# uController_n_Ethernet.net
KiCad netlist of a schematic drawn in Altium Designer
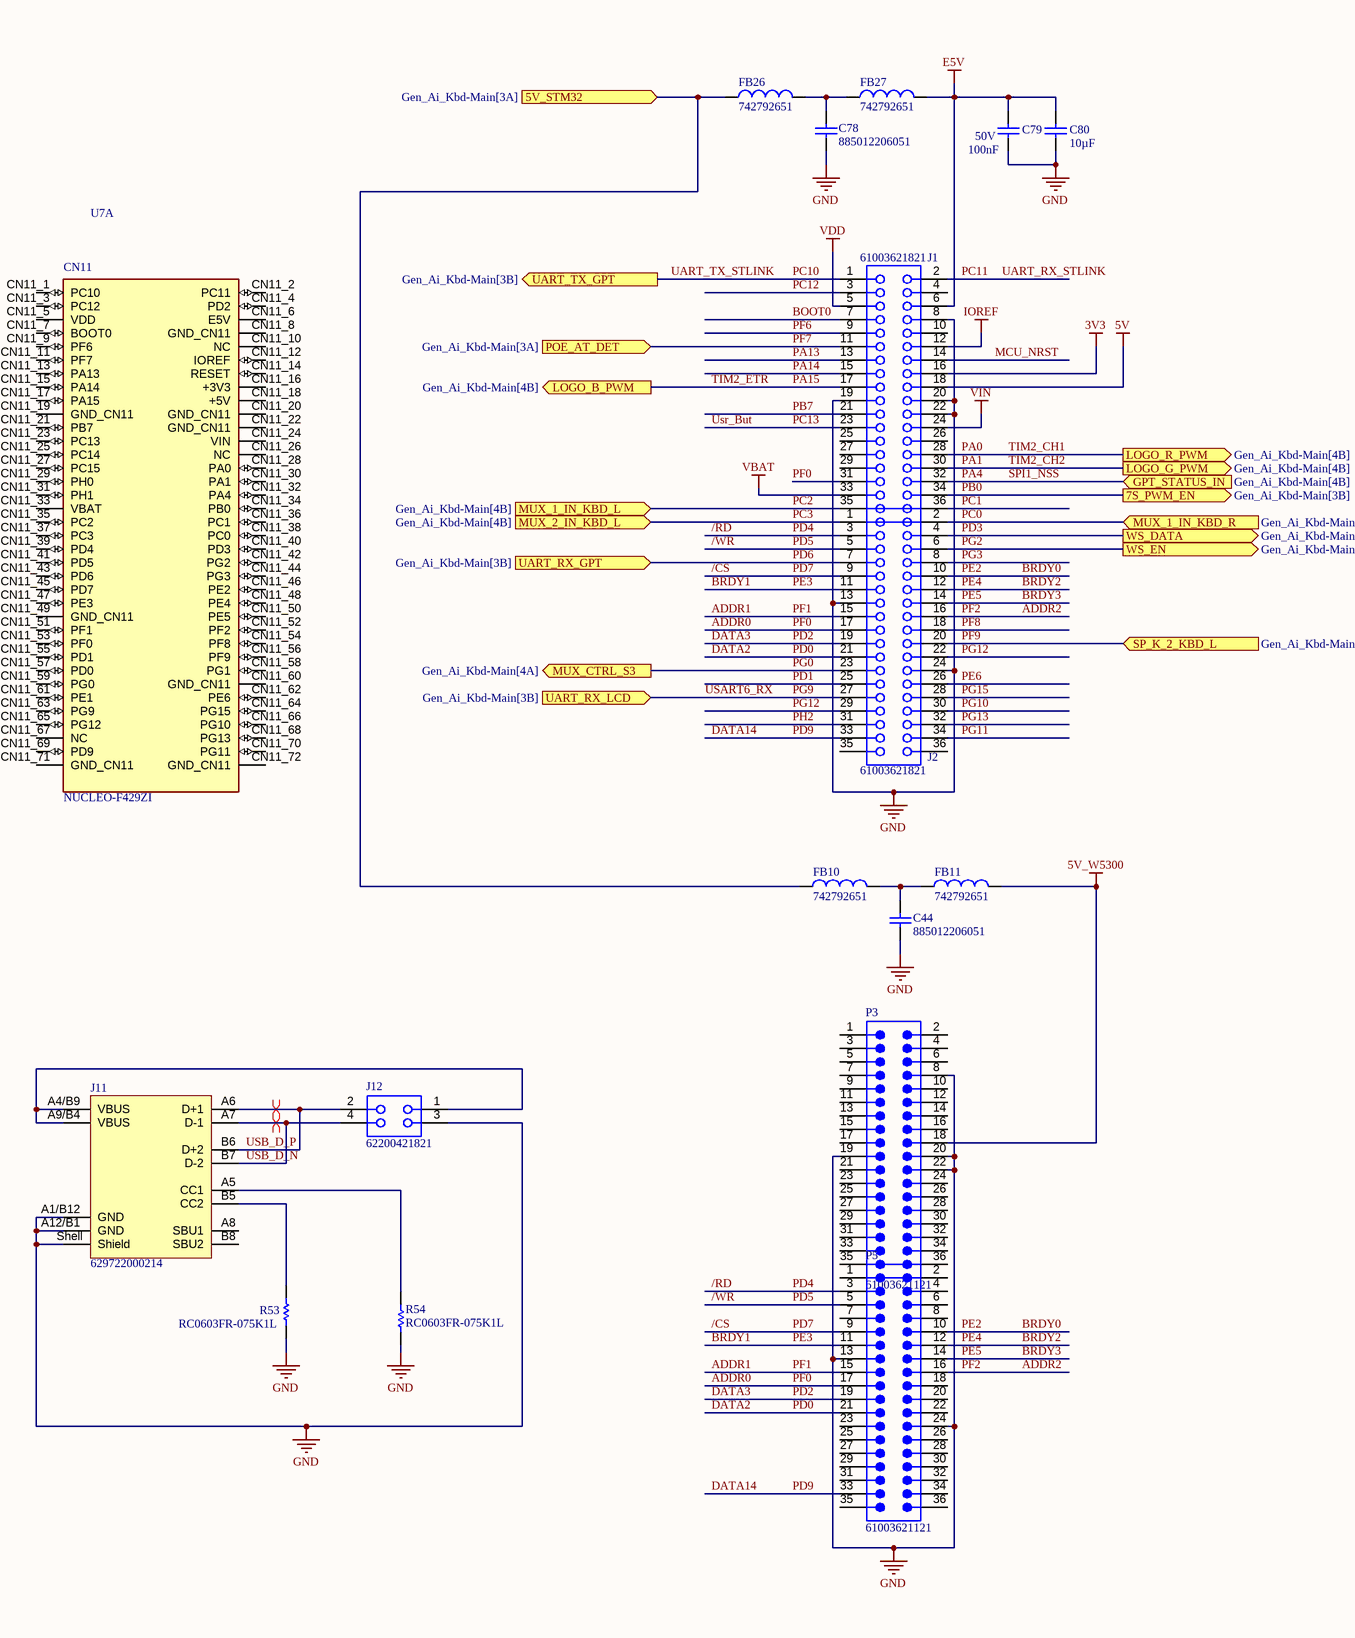
[diagram p0: uController_n_Ethernet.SchDoc, left]
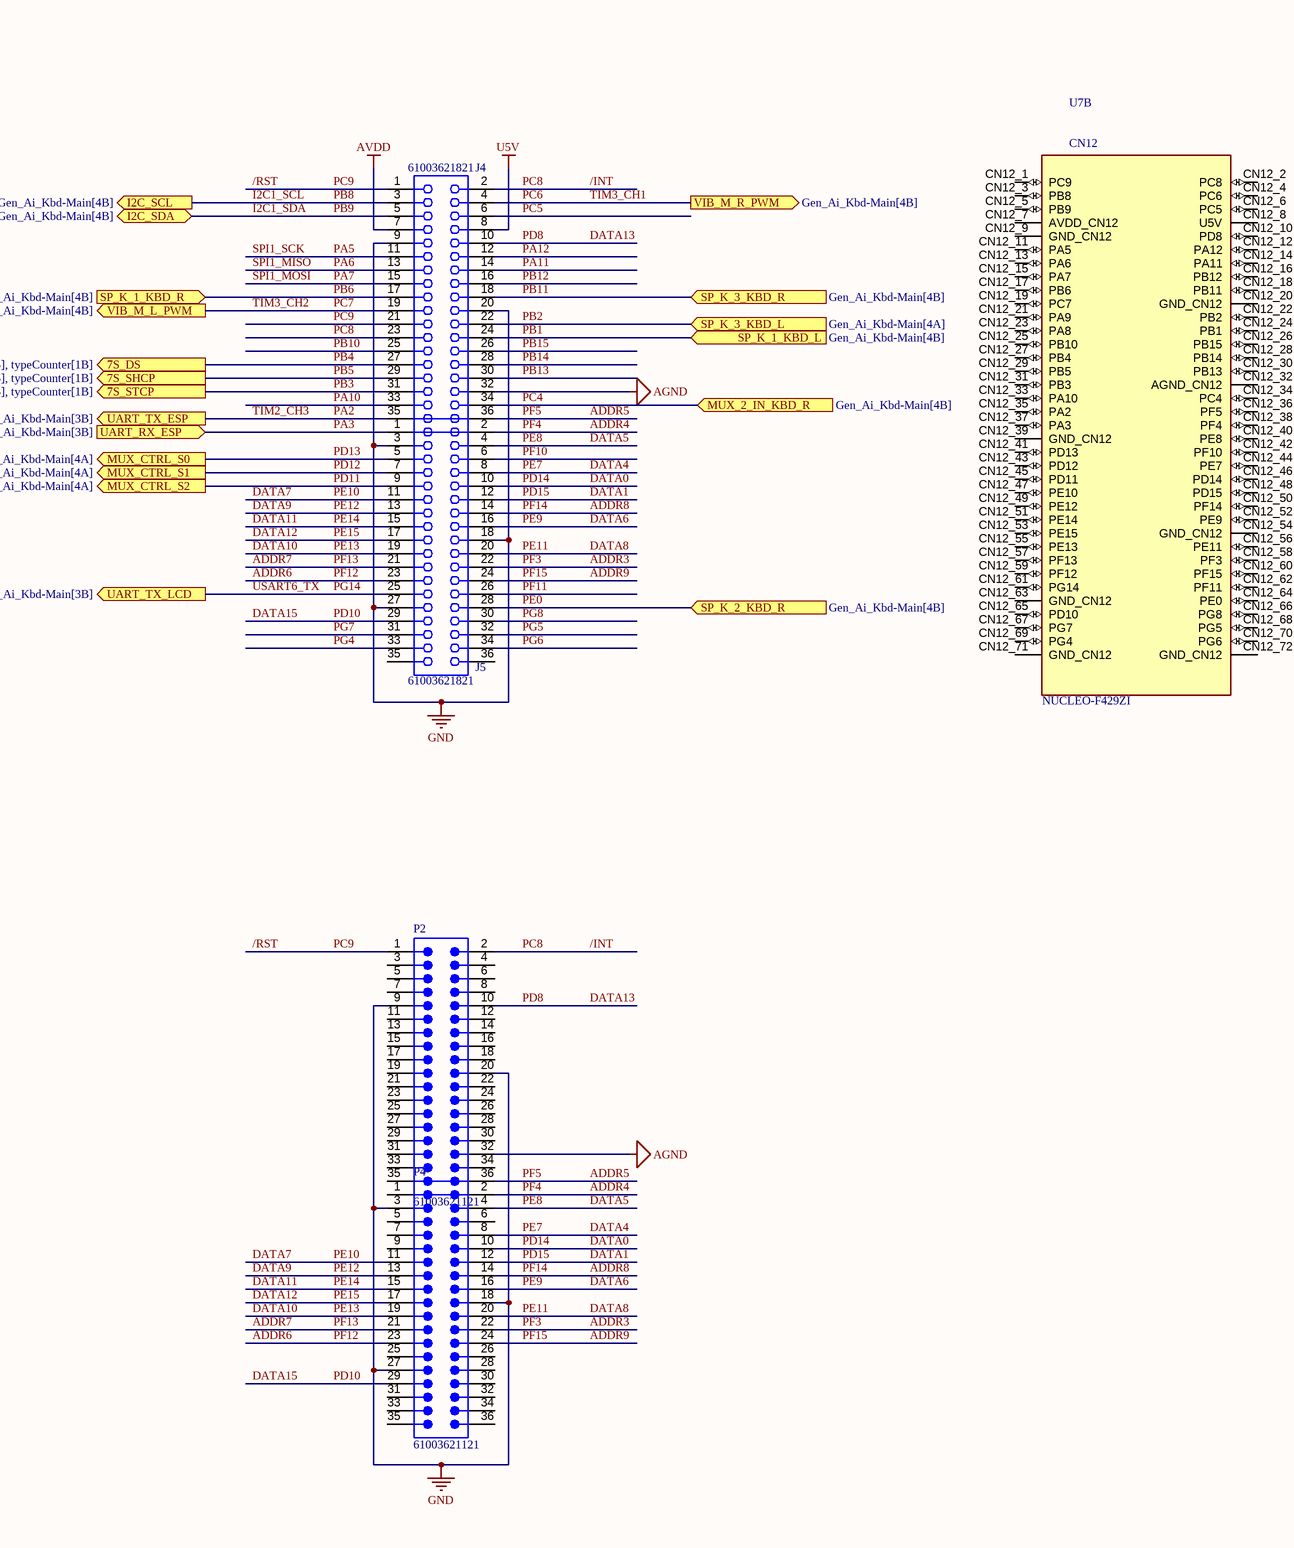
[diagram p1: uController_n_Ethernet.SchDoc, right]

(export (version "E")
  (design (tool "Eeschema 10.0.6"))
  (components
    (comp (ref "C44")
      (value "885012206051")
      (footprint "WCAP-CSGP_0603_L1.6W0.8H0.8_Reflow")
      (description "885012206051 Cap Cer 0.68UF 16V X7R 0603")
      (fields (field (name "TOLERANCE") "10%"))
      (libsource (lib "Altium Content Vault") (part "Capacitor_Non-Polarized"))
    )
    (comp (ref "C78")
      (value "885012206051")
      (footprint "WCAP-CSGP_0603_L1.6W0.8H0.8_Reflow")
      (description "885012206051 Cap Cer 0.68UF 16V X7R 0603")
      (fields (field (name "TOLERANCE") "10%"))
      (libsource (lib "Altium Content Vault") (part "Capacitor_Non-Polarized"))
    )
    (comp (ref "C79")
      (value "885012206095")
      (footprint "WCAP-CSGP_0603_L1.6W0.8H0.8_Reflow")
      (description "WCAP-CSGP Multilayer Ceramic Chip Capacitor, General Purpose, size 0603, X7R, 100nF, 50VDC")
      (fields
        (field (name "CAPACITANCE") "100nF")
        (field (name "MANUFACTURER") "Wurth Elektronik")
        (field (name "RATED VOLTAGE (DC)") "50V")
      )
      (libsource (lib "Test365") (part "885012209047R"))
    )
    (comp (ref "C80")
      (value "885012106006")
      (footprint "WCAP-CSGP_0603_L1.6W0.8H0.8_Reflow")
      (description "WCAP-CSGP Multilayer Ceramic Chip Capacitor, General Purpose, size 0603, X5R, 10µF, 6.3VDC")
      (fields (field (name "MANUFACTURER") "Wurth Elektronik") (field (name "CAPACITANCE") "10µF"))
      (libsource (lib "Test365") (part "885012209047R"))
    )
    (comp (ref "FB10")
      (value "742792651")
      (footprint "WE-CBF_0603_L1.6W0.8H0.8_HC")
      (fields (field (name "TOLERANCE") "25%"))
      (libsource (lib "Altium Content Vault") (part "Ferrite"))
    )
    (comp (ref "FB11")
      (value "742792651")
      (footprint "WE-CBF_0603_L1.6W0.8H0.8_HC")
      (fields (field (name "TOLERANCE") "25%"))
      (libsource (lib "Altium Content Vault") (part "Ferrite"))
    )
    (comp (ref "FB26")
      (value "742792651")
      (footprint "WE-CBF_0603_L1.6W0.8H0.8_HC")
      (fields (field (name "TOLERANCE") "25%"))
      (libsource (lib "Altium Content Vault") (part "Ferrite"))
    )
    (comp (ref "FB27")
      (value "742792651")
      (footprint "WE-CBF_0603_L1.6W0.8H0.8_HC")
      (fields (field (name "TOLERANCE") "25%"))
      (libsource (lib "Altium Content Vault") (part "Ferrite"))
    )
    (comp (ref "J1")
      (value "61003621821")
      (footprint "61003621821")
      (libsource (lib "Altium Content Vault") (part "Header_Female_2R_36P"))
    )
    (comp (ref "J2")
      (value "61003621821")
      (footprint "61003621821")
      (libsource (lib "Altium Content Vault") (part "Header_Female_2R_36P"))
    )
    (comp (ref "J4")
      (value "61003621821")
      (footprint "61003621821")
      (libsource (lib "Altium Content Vault") (part "Header_Female_2R_36P"))
    )
    (comp (ref "J5")
      (value "61003621821")
      (footprint "61003621821")
      (libsource (lib "Altium Content Vault") (part "Header_Female_2R_36P"))
    )
    (comp (ref "J11")
      (value "629722000214")
      (footprint "629722000214")
      (description "Conenctor USB 2.0 Type C Horizontal SMT")
      (libsource (lib "Altium Content Vault") (part "USB 2.0_Type C_Receptacle_1 Port_629722000214"))
    )
    (comp (ref "J12")
      (value "62200421821")
      (footprint "62200421821")
      (libsource (lib "Altium Content Vault") (part "Header_Female_2R_04P"))
    )
    (comp (ref "P2")
      (value "61003621121")
      (footprint "61003621121")
      (libsource (lib "Altium Content Vault") (part "Header_Male_2R_36P"))
    )
    (comp (ref "P3")
      (value "61003621121")
      (footprint "61003621121")
      (libsource (lib "Altium Content Vault") (part "Header_Male_2R_36P"))
    )
    (comp (ref "P4")
      (value "61003621121")
      (footprint "61003621121")
      (libsource (lib "Altium Content Vault") (part "Header_Male_2R_36P"))
    )
    (comp (ref "P5")
      (value "61003621121")
      (footprint "61003621121")
      (libsource (lib "Altium Content Vault") (part "Header_Male_2R_36P"))
    )
    (comp (ref "R53")
      (value "RC0603FR-075K1L")
      (footprint "RESC1608X55X25ML10T15")
      (fields (field (name "MANUFACTURER") "Yageo"))
      (libsource (lib "Altium Content Vault") (part "RES"))
    )
    (comp (ref "R54")
      (value "RC0603FR-075K1L")
      (footprint "RESC1608X55X25ML10T15")
      (fields (field (name "MANUFACTURER") "Yageo"))
      (libsource (lib "Altium Content Vault") (part "RES"))
    )
    (comp (ref "U7")
      (value "NUCLEO-F429ZI")
      (footprint "MODULE_NUCLEO-F429ZI")
      (fields (field (name "MF") "STMicroelectronics"))
      (libsource (lib "Test365") (part "NUCLEO-F429ZI"))
    )
  )
  (nets
    (net (code "1") (name "/5V_STM32") (class "Default")
      (node (ref "FB10") (pin "1") (pinfunction "1_1") (pintype "passive"))
      (node (ref "FB26") (pin "1") (pinfunction "1_1") (pintype "passive"))
    )
    (net (code "2") (name "/ADDR0") (class "Default")
      (node (ref "J1") (pin "31") (pinfunction "31_31") (pintype "passive"))
      (node (ref "J2") (pin "17") (pinfunction "17_17") (pintype "passive"))
      (node (ref "P5") (pin "17") (pinfunction "17_17") (pintype "passive"))
    )
    (net (code "3") (name "/ADDR1") (class "Default")
      (node (ref "J2") (pin "15") (pinfunction "15_15") (pintype "passive"))
      (node (ref "P5") (pin "15") (pinfunction "15_15") (pintype "passive"))
    )
    (net (code "4") (name "/ADDR2") (class "Default")
      (node (ref "J2") (pin "16") (pinfunction "16_16") (pintype "passive"))
      (node (ref "P5") (pin "16") (pinfunction "16_16") (pintype "passive"))
    )
    (net (code "5") (name "/ADDR3") (class "Default")
      (node (ref "J5") (pin "22") (pinfunction "22_22") (pintype "passive"))
      (node (ref "P4") (pin "22") (pinfunction "22_22") (pintype "passive"))
    )
    (net (code "6") (name "/ADDR4") (class "Default")
      (node (ref "J5") (pin "2") (pinfunction "2_2") (pintype "passive"))
      (node (ref "P4") (pin "2") (pinfunction "2_2") (pintype "passive"))
    )
    (net (code "7") (name "/ADDR5") (class "Default")
      (node (ref "J4") (pin "36") (pinfunction "36_36") (pintype "passive"))
      (node (ref "P2") (pin "36") (pinfunction "36_36") (pintype "passive"))
    )
    (net (code "8") (name "/ADDR6") (class "Default")
      (node (ref "J5") (pin "23") (pinfunction "23_23") (pintype "passive"))
      (node (ref "P4") (pin "23") (pinfunction "23_23") (pintype "passive"))
    )
    (net (code "9") (name "/ADDR7") (class "Default")
      (node (ref "J5") (pin "21") (pinfunction "21_21") (pintype "passive"))
      (node (ref "P4") (pin "21") (pinfunction "21_21") (pintype "passive"))
    )
    (net (code "10") (name "/ADDR8") (class "Default")
      (node (ref "J5") (pin "14") (pinfunction "14_14") (pintype "passive"))
      (node (ref "P4") (pin "14") (pinfunction "14_14") (pintype "passive"))
    )
    (net (code "11") (name "/ADDR9") (class "Default")
      (node (ref "J5") (pin "24") (pinfunction "24_24") (pintype "passive"))
      (node (ref "P4") (pin "24") (pinfunction "24_24") (pintype "passive"))
    )
    (net (code "12") (name "/BOOT0") (class "Default")
      (node (ref "J1") (pin "7") (pinfunction "7_7") (pintype "passive"))
    )
    (net (code "13") (name "/BRDY0") (class "Default")
      (node (ref "J2") (pin "10") (pinfunction "10_10") (pintype "passive"))
      (node (ref "P5") (pin "10") (pinfunction "10_10") (pintype "passive"))
    )
    (net (code "14") (name "/BRDY1") (class "Default")
      (node (ref "J2") (pin "11") (pinfunction "11_11") (pintype "passive"))
      (node (ref "P5") (pin "11") (pinfunction "11_11") (pintype "passive"))
    )
    (net (code "15") (name "/BRDY2") (class "Default")
      (node (ref "J2") (pin "12") (pinfunction "12_12") (pintype "passive"))
      (node (ref "P5") (pin "12") (pinfunction "12_12") (pintype "passive"))
    )
    (net (code "16") (name "/BRDY3") (class "Default")
      (node (ref "J2") (pin "14") (pinfunction "14_14") (pintype "passive"))
      (node (ref "P5") (pin "14") (pinfunction "14_14") (pintype "passive"))
    )
    (net (code "17") (name "/DATA0") (class "Default")
      (node (ref "J5") (pin "10") (pinfunction "10_10") (pintype "passive"))
      (node (ref "P4") (pin "10") (pinfunction "10_10") (pintype "passive"))
    )
    (net (code "18") (name "/DATA1") (class "Default")
      (node (ref "J5") (pin "12") (pinfunction "12_12") (pintype "passive"))
      (node (ref "P4") (pin "12") (pinfunction "12_12") (pintype "passive"))
    )
    (net (code "19") (name "/DATA2") (class "Default")
      (node (ref "J2") (pin "21") (pinfunction "21_21") (pintype "passive"))
      (node (ref "P5") (pin "21") (pinfunction "21_21") (pintype "passive"))
    )
    (net (code "20") (name "/DATA3") (class "Default")
      (node (ref "J2") (pin "19") (pinfunction "19_19") (pintype "passive"))
      (node (ref "P5") (pin "19") (pinfunction "19_19") (pintype "passive"))
    )
    (net (code "21") (name "/DATA4") (class "Default")
      (node (ref "J5") (pin "8") (pinfunction "8_8") (pintype "passive"))
      (node (ref "P4") (pin "8") (pinfunction "8_8") (pintype "passive"))
    )
    (net (code "22") (name "/DATA5") (class "Default")
      (node (ref "J5") (pin "4") (pinfunction "4_4") (pintype "passive"))
      (node (ref "P4") (pin "4") (pinfunction "4_4") (pintype "passive"))
    )
    (net (code "23") (name "/DATA6") (class "Default")
      (node (ref "J5") (pin "16") (pinfunction "16_16") (pintype "passive"))
      (node (ref "P4") (pin "16") (pinfunction "16_16") (pintype "passive"))
    )
    (net (code "24") (name "/DATA7") (class "Default")
      (node (ref "J5") (pin "11") (pinfunction "11_11") (pintype "passive"))
      (node (ref "P4") (pin "11") (pinfunction "11_11") (pintype "passive"))
    )
    (net (code "25") (name "/DATA8") (class "Default")
      (node (ref "J5") (pin "20") (pinfunction "20_20") (pintype "passive"))
      (node (ref "P4") (pin "20") (pinfunction "20_20") (pintype "passive"))
    )
    (net (code "26") (name "/DATA9") (class "Default")
      (node (ref "J5") (pin "13") (pinfunction "13_13") (pintype "passive"))
      (node (ref "P4") (pin "13") (pinfunction "13_13") (pintype "passive"))
    )
    (net (code "27") (name "/DATA10") (class "Default")
      (node (ref "J5") (pin "19") (pinfunction "19_19") (pintype "passive"))
      (node (ref "P4") (pin "19") (pinfunction "19_19") (pintype "passive"))
    )
    (net (code "28") (name "/DATA11") (class "Default")
      (node (ref "J5") (pin "15") (pinfunction "15_15") (pintype "passive"))
      (node (ref "P4") (pin "15") (pinfunction "15_15") (pintype "passive"))
    )
    (net (code "29") (name "/DATA12") (class "Default")
      (node (ref "J5") (pin "17") (pinfunction "17_17") (pintype "passive"))
      (node (ref "P4") (pin "17") (pinfunction "17_17") (pintype "passive"))
    )
    (net (code "30") (name "/DATA13") (class "Default")
      (node (ref "J4") (pin "10") (pinfunction "10_10") (pintype "passive"))
      (node (ref "P2") (pin "10") (pinfunction "10_10") (pintype "passive"))
    )
    (net (code "31") (name "/DATA14") (class "Default")
      (node (ref "J2") (pin "33") (pinfunction "33_33") (pintype "passive"))
      (node (ref "P5") (pin "33") (pinfunction "33_33") (pintype "passive"))
    )
    (net (code "32") (name "/DATA15") (class "Default")
      (node (ref "J5") (pin "29") (pinfunction "29_29") (pintype "passive"))
      (node (ref "P4") (pin "29") (pinfunction "29_29") (pintype "passive"))
    )
    (net (code "33") (name "/I2C1_SCL") (class "Default")
      (node (ref "J4") (pin "3") (pinfunction "3_3") (pintype "passive"))
    )
    (net (code "34") (name "/I2C1_SDA") (class "Default")
      (node (ref "J4") (pin "5") (pinfunction "5_5") (pintype "passive"))
    )
    (net (code "35") (name "/MCU_NRST") (class "Default")
      (node (ref "J1") (pin "14") (pinfunction "14_14") (pintype "passive"))
    )
    (net (code "36") (name "/PA0") (class "Default")
      (node (ref "J1") (pin "28") (pinfunction "28_28") (pintype "passive"))
    )
    (net (code "37") (name "/PA1") (class "Default")
      (node (ref "J1") (pin "30") (pinfunction "30_30") (pintype "passive"))
    )
    (net (code "38") (name "/PA2") (class "Default")
      (node (ref "J4") (pin "35") (pinfunction "35_35") (pintype "passive"))
    )
    (net (code "39") (name "/PA3") (class "Default")
      (node (ref "J5") (pin "1") (pinfunction "1_1") (pintype "passive"))
    )
    (net (code "40") (name "/PA4") (class "Default")
      (node (ref "J1") (pin "32") (pinfunction "32_32") (pintype "passive"))
    )
    (net (code "41") (name "/PA5") (class "Default")
      (node (ref "J4") (pin "11") (pinfunction "11_11") (pintype "passive"))
    )
    (net (code "42") (name "/PA6") (class "Default")
      (node (ref "J4") (pin "13") (pinfunction "13_13") (pintype "passive"))
    )
    (net (code "43") (name "/PA7") (class "Default")
      (node (ref "J4") (pin "15") (pinfunction "15_15") (pintype "passive"))
    )
    (net (code "44") (name "/PA10") (class "Default")
      (node (ref "J4") (pin "33") (pinfunction "33_33") (pintype "passive"))
    )
    (net (code "45") (name "/PA11") (class "Default")
      (node (ref "J4") (pin "14") (pinfunction "14_14") (pintype "passive"))
    )
    (net (code "46") (name "/PA12") (class "Default")
      (node (ref "J4") (pin "12") (pinfunction "12_12") (pintype "passive"))
    )
    (net (code "47") (name "/PA13") (class "Default")
      (node (ref "J1") (pin "13") (pinfunction "13_13") (pintype "passive"))
    )
    (net (code "48") (name "/PA14") (class "Default")
      (node (ref "J1") (pin "15") (pinfunction "15_15") (pintype "passive"))
    )
    (net (code "49") (name "/PA15") (class "Default")
      (node (ref "J1") (pin "17") (pinfunction "17_17") (pintype "passive"))
    )
    (net (code "50") (name "/PB0") (class "Default")
      (node (ref "J1") (pin "34") (pinfunction "34_34") (pintype "passive"))
    )
    (net (code "51") (name "/PB1") (class "Default")
      (node (ref "J4") (pin "24") (pinfunction "24_24") (pintype "passive"))
    )
    (net (code "52") (name "/PB2") (class "Default")
      (node (ref "J4") (pin "22") (pinfunction "22_22") (pintype "passive"))
    )
    (net (code "53") (name "/PB3") (class "Default")
      (node (ref "J4") (pin "31") (pinfunction "31_31") (pintype "passive"))
    )
    (net (code "54") (name "/PB4") (class "Default")
      (node (ref "J4") (pin "27") (pinfunction "27_27") (pintype "passive"))
    )
    (net (code "55") (name "/PB5") (class "Default")
      (node (ref "J4") (pin "29") (pinfunction "29_29") (pintype "passive"))
    )
    (net (code "56") (name "/PB6") (class "Default")
      (node (ref "J4") (pin "17") (pinfunction "17_17") (pintype "passive"))
    )
    (net (code "57") (name "/PB7") (class "Default")
      (node (ref "J1") (pin "21") (pinfunction "21_21") (pintype "passive"))
    )
    (net (code "58") (name "/PB10") (class "Default")
      (node (ref "J4") (pin "25") (pinfunction "25_25") (pintype "passive"))
    )
    (net (code "59") (name "/PB11") (class "Default")
      (node (ref "J4") (pin "18") (pinfunction "18_18") (pintype "passive"))
    )
    (net (code "60") (name "/PB12") (class "Default")
      (node (ref "J4") (pin "16") (pinfunction "16_16") (pintype "passive"))
    )
    (net (code "61") (name "/PB13") (class "Default")
      (node (ref "J4") (pin "30") (pinfunction "30_30") (pintype "passive"))
    )
    (net (code "62") (name "/PB14") (class "Default")
      (node (ref "J4") (pin "28") (pinfunction "28_28") (pintype "passive"))
    )
    (net (code "63") (name "/PB15") (class "Default")
      (node (ref "J4") (pin "26") (pinfunction "26_26") (pintype "passive"))
    )
    (net (code "64") (name "/PC0") (class "Default")
      (node (ref "J2") (pin "2") (pinfunction "2_2") (pintype "passive"))
    )
    (net (code "65") (name "/PC1") (class "Default")
      (node (ref "J1") (pin "36") (pinfunction "36_36") (pintype "passive"))
    )
    (net (code "66") (name "/PC2") (class "Default")
      (node (ref "J1") (pin "35") (pinfunction "35_35") (pintype "passive"))
    )
    (net (code "67") (name "/PC3") (class "Default")
      (node (ref "J2") (pin "1") (pinfunction "1_1") (pintype "passive"))
    )
    (net (code "68") (name "/PC4") (class "Default")
      (node (ref "J4") (pin "34") (pinfunction "34_34") (pintype "passive"))
    )
    (net (code "69") (name "/PC5") (class "Default")
      (node (ref "J4") (pin "6") (pinfunction "6_6") (pintype "passive"))
    )
    (net (code "70") (name "/PC6") (class "Default")
      (node (ref "J4") (pin "4") (pinfunction "4_4") (pintype "passive"))
    )
    (net (code "71") (name "/PC7") (class "Default")
      (node (ref "J4") (pin "19") (pinfunction "19_19") (pintype "passive"))
    )
    (net (code "72") (name "/PC8") (class "Default")
      (node (ref "J4") (pin "2") (pinfunction "2_2") (pintype "passive"))
      (node (ref "J4") (pin "23") (pinfunction "23_23") (pintype "passive"))
      (node (ref "P2") (pin "2") (pinfunction "2_2") (pintype "passive"))
    )
    (net (code "73") (name "/PC9") (class "Default")
      (node (ref "J4") (pin "1") (pinfunction "1_1") (pintype "passive"))
      (node (ref "J4") (pin "21") (pinfunction "21_21") (pintype "passive"))
      (node (ref "P2") (pin "1") (pinfunction "1_1") (pintype "passive"))
    )
    (net (code "74") (name "/PC10") (class "Default")
      (node (ref "J1") (pin "1") (pinfunction "1_1") (pintype "passive"))
    )
    (net (code "75") (name "/PC11") (class "Default")
      (node (ref "J1") (pin "2") (pinfunction "2_2") (pintype "passive"))
    )
    (net (code "76") (name "/PC12") (class "Default")
      (node (ref "J1") (pin "3") (pinfunction "3_3") (pintype "passive"))
    )
    (net (code "77") (name "/PC13") (class "Default")
      (node (ref "J1") (pin "23") (pinfunction "23_23") (pintype "passive"))
    )
    (net (code "78") (name "/PD1") (class "Default")
      (node (ref "J2") (pin "25") (pinfunction "25_25") (pintype "passive"))
    )
    (net (code "79") (name "/PD3") (class "Default")
      (node (ref "J2") (pin "4") (pinfunction "4_4") (pintype "passive"))
    )
    (net (code "80") (name "/PD4") (class "Default")
      (node (ref "J2") (pin "3") (pinfunction "3_3") (pintype "passive"))
      (node (ref "P5") (pin "3") (pinfunction "3_3") (pintype "passive"))
    )
    (net (code "81") (name "/PD5") (class "Default")
      (node (ref "J2") (pin "5") (pinfunction "5_5") (pintype "passive"))
      (node (ref "P5") (pin "5") (pinfunction "5_5") (pintype "passive"))
    )
    (net (code "82") (name "/PD6") (class "Default")
      (node (ref "J2") (pin "7") (pinfunction "7_7") (pintype "passive"))
    )
    (net (code "83") (name "/PD7") (class "Default")
      (node (ref "J2") (pin "9") (pinfunction "9_9") (pintype "passive"))
      (node (ref "P5") (pin "9") (pinfunction "9_9") (pintype "passive"))
    )
    (net (code "84") (name "/PD11") (class "Default")
      (node (ref "J5") (pin "9") (pinfunction "9_9") (pintype "passive"))
    )
    (net (code "85") (name "/PD12") (class "Default")
      (node (ref "J5") (pin "7") (pinfunction "7_7") (pintype "passive"))
    )
    (net (code "86") (name "/PD13") (class "Default")
      (node (ref "J5") (pin "5") (pinfunction "5_5") (pintype "passive"))
    )
    (net (code "87") (name "/PE0") (class "Default")
      (node (ref "J5") (pin "28") (pinfunction "28_28") (pintype "passive"))
    )
    (net (code "88") (name "/PE6") (class "Default")
      (node (ref "J2") (pin "26") (pinfunction "26_26") (pintype "passive"))
    )
    (net (code "89") (name "/PF6") (class "Default")
      (node (ref "J1") (pin "9") (pinfunction "9_9") (pintype "passive"))
    )
    (net (code "90") (name "/PF7") (class "Default")
      (node (ref "J1") (pin "11") (pinfunction "11_11") (pintype "passive"))
    )
    (net (code "91") (name "/PF8") (class "Default")
      (node (ref "J2") (pin "18") (pinfunction "18_18") (pintype "passive"))
    )
    (net (code "92") (name "/PF9") (class "Default")
      (node (ref "J2") (pin "20") (pinfunction "20_20") (pintype "passive"))
    )
    (net (code "93") (name "/PF10") (class "Default")
      (node (ref "J5") (pin "6") (pinfunction "6_6") (pintype "passive"))
    )
    (net (code "94") (name "/PF11") (class "Default")
      (node (ref "J5") (pin "26") (pinfunction "26_26") (pintype "passive"))
    )
    (net (code "95") (name "/PG0") (class "Default")
      (node (ref "J2") (pin "23") (pinfunction "23_23") (pintype "passive"))
    )
    (net (code "96") (name "/PG2") (class "Default")
      (node (ref "J2") (pin "6") (pinfunction "6_6") (pintype "passive"))
    )
    (net (code "97") (name "/PG3") (class "Default")
      (node (ref "J2") (pin "8") (pinfunction "8_8") (pintype "passive"))
    )
    (net (code "98") (name "/PG4") (class "Default")
      (node (ref "J5") (pin "33") (pinfunction "33_33") (pintype "passive"))
    )
    (net (code "99") (name "/PG5") (class "Default")
      (node (ref "J5") (pin "32") (pinfunction "32_32") (pintype "passive"))
    )
    (net (code "100") (name "/PG6") (class "Default")
      (node (ref "J5") (pin "34") (pinfunction "34_34") (pintype "passive"))
    )
    (net (code "101") (name "/PG7") (class "Default")
      (node (ref "J5") (pin "31") (pinfunction "31_31") (pintype "passive"))
    )
    (net (code "102") (name "/PG8") (class "Default")
      (node (ref "J5") (pin "30") (pinfunction "30_30") (pintype "passive"))
    )
    (net (code "103") (name "/PG9") (class "Default")
      (node (ref "J2") (pin "27") (pinfunction "27_27") (pintype "passive"))
    )
    (net (code "104") (name "/PG10") (class "Default")
      (node (ref "J2") (pin "30") (pinfunction "30_30") (pintype "passive"))
    )
    (net (code "105") (name "/PG11") (class "Default")
      (node (ref "J2") (pin "34") (pinfunction "34_34") (pintype "passive"))
    )
    (net (code "106") (name "/PG12") (class "Default")
      (node (ref "J2") (pin "22") (pinfunction "22_22") (pintype "passive"))
      (node (ref "J2") (pin "29") (pinfunction "29_29") (pintype "passive"))
    )
    (net (code "107") (name "/PG13") (class "Default")
      (node (ref "J2") (pin "32") (pinfunction "32_32") (pintype "passive"))
    )
    (net (code "108") (name "/PG14") (class "Default")
      (node (ref "J5") (pin "25") (pinfunction "25_25") (pintype "passive"))
    )
    (net (code "109") (name "/PG15") (class "Default")
      (node (ref "J2") (pin "28") (pinfunction "28_28") (pintype "passive"))
    )
    (net (code "110") (name "/PH2") (class "Default")
      (node (ref "J2") (pin "31") (pinfunction "31_31") (pintype "passive"))
    )
    (net (code "111") (name "/USB_D_N") (class "Default")
      (node (ref "J11") (pin "A7") (pinfunction "D-1_A7") (pintype "passive"))
      (node (ref "J11") (pin "B7") (pinfunction "D-2_B7") (pintype "passive"))
      (node (ref "J12") (pin "4") (pinfunction "4_4") (pintype "passive"))
    )
    (net (code "112") (name "/USB_D_P") (class "Default")
      (node (ref "J11") (pin "A6") (pinfunction "D+1_A6") (pintype "passive"))
      (node (ref "J11") (pin "B6") (pinfunction "D+2_B6") (pintype "passive"))
      (node (ref "J12") (pin "2") (pinfunction "2_2") (pintype "passive"))
    )
    (net (code "113") (name "3V3") (class "Default")
      (node (ref "J1") (pin "16") (pinfunction "16_16") (pintype "passive"))
    )
    (net (code "114") (name "5V") (class "Default")
      (node (ref "J1") (pin "18") (pinfunction "18_18") (pintype "passive"))
    )
    (net (code "115") (name "5V_W5300") (class "Default")
      (node (ref "FB11") (pin "2") (pinfunction "2_2") (pintype "passive"))
      (node (ref "P3") (pin "18") (pinfunction "18_18") (pintype "passive"))
    )
    (net (code "116") (name "AGND") (class "Default")
      (node (ref "J4") (pin "32") (pinfunction "32_32") (pintype "passive"))
      (node (ref "P2") (pin "32") (pinfunction "32_32") (pintype "passive"))
    )
    (net (code "117") (name "AVDD") (class "Default")
      (node (ref "J4") (pin "7") (pinfunction "7_7") (pintype "passive"))
    )
    (net (code "118") (name "E5V") (class "Default")
      (node (ref "C79") (pin "2") (pinfunction "2_2") (pintype "passive"))
      (node (ref "C80") (pin "2") (pinfunction "2_2") (pintype "passive"))
      (node (ref "FB27") (pin "2") (pinfunction "2_2") (pintype "passive"))
      (node (ref "J1") (pin "6") (pinfunction "6_6") (pintype "passive"))
    )
    (net (code "119") (name "GND") (class "Default")
      (node (ref "C44") (pin "1") (pinfunction "1_1") (pintype "passive"))
      (node (ref "C78") (pin "1") (pinfunction "1_1") (pintype "passive"))
      (node (ref "C79") (pin "1") (pinfunction "1_1") (pintype "passive"))
      (node (ref "C80") (pin "1") (pinfunction "1_1") (pintype "passive"))
      (node (ref "J1") (pin "19") (pinfunction "19_19") (pintype "passive"))
      (node (ref "J1") (pin "20") (pinfunction "20_20") (pintype "passive"))
      (node (ref "J1") (pin "22") (pinfunction "22_22") (pintype "passive"))
      (node (ref "J1") (pin "8") (pinfunction "8_8") (pintype "passive"))
      (node (ref "J11") (pin "A1/B12") (pinfunction "GND_A1/B12") (pintype "passive"))
      (node (ref "J11") (pin "A12/B1") (pinfunction "GND_A12/B1") (pintype "passive"))
      (node (ref "J11") (pin "Shell") (pinfunction "Shield_Shell") (pintype "passive"))
      (node (ref "J12") (pin "3") (pinfunction "3_3") (pintype "passive"))
      (node (ref "J2") (pin "13") (pinfunction "13_13") (pintype "passive"))
      (node (ref "J2") (pin "24") (pinfunction "24_24") (pintype "passive"))
      (node (ref "J4") (pin "20") (pinfunction "20_20") (pintype "passive"))
      (node (ref "J4") (pin "9") (pinfunction "9_9") (pintype "passive"))
      (node (ref "J5") (pin "18") (pinfunction "18_18") (pintype "passive"))
      (node (ref "J5") (pin "27") (pinfunction "27_27") (pintype "passive"))
      (node (ref "J5") (pin "3") (pinfunction "3_3") (pintype "passive"))
      (node (ref "P2") (pin "20") (pinfunction "20_20") (pintype "passive"))
      (node (ref "P2") (pin "9") (pinfunction "9_9") (pintype "passive"))
      (node (ref "P3") (pin "19") (pinfunction "19_19") (pintype "passive"))
      (node (ref "P3") (pin "20") (pinfunction "20_20") (pintype "passive"))
      (node (ref "P3") (pin "22") (pinfunction "22_22") (pintype "passive"))
      (node (ref "P3") (pin "8") (pinfunction "8_8") (pintype "passive"))
      (node (ref "P4") (pin "18") (pinfunction "18_18") (pintype "passive"))
      (node (ref "P4") (pin "27") (pinfunction "27_27") (pintype "passive"))
      (node (ref "P4") (pin "3") (pinfunction "3_3") (pintype "passive"))
      (node (ref "P5") (pin "13") (pinfunction "13_13") (pintype "passive"))
      (node (ref "P5") (pin "24") (pinfunction "24_24") (pintype "passive"))
      (node (ref "R53") (pin "1") (pinfunction "1_1") (pintype "passive"))
      (node (ref "R54") (pin "1") (pinfunction "1_1") (pintype "passive"))
    )
    (net (code "120") (name "IOREF") (class "Default")
      (node (ref "J1") (pin "12") (pinfunction "12_12") (pintype "passive"))
    )
    (net (code "121") (name "Net-(C44-Pad2)") (class "Default")
      (node (ref "C44") (pin "2") (pinfunction "2_2") (pintype "passive"))
      (node (ref "FB10") (pin "2") (pinfunction "2_2") (pintype "passive"))
      (node (ref "FB11") (pin "1") (pinfunction "1_1") (pintype "passive"))
    )
    (net (code "122") (name "Net-(C78-Pad2)") (class "Default")
      (node (ref "C78") (pin "2") (pinfunction "2_2") (pintype "passive"))
      (node (ref "FB26") (pin "2") (pinfunction "2_2") (pintype "passive"))
      (node (ref "FB27") (pin "1") (pinfunction "1_1") (pintype "passive"))
    )
    (net (code "123") (name "Net-(J11-CC1)") (class "Default")
      (node (ref "J11") (pin "A5") (pinfunction "CC1_A5") (pintype "passive"))
      (node (ref "R54") (pin "2") (pinfunction "2_2") (pintype "passive"))
    )
    (net (code "124") (name "Net-(J11-CC2)") (class "Default")
      (node (ref "J11") (pin "B5") (pinfunction "CC2_B5") (pintype "passive"))
      (node (ref "R53") (pin "2") (pinfunction "2_2") (pintype "passive"))
    )
    (net (code "125") (name "Net-(J11-VBUS-PadA4{slash}B9)") (class "Default")
      (node (ref "J11") (pin "A4/B9") (pinfunction "VBUS_A4/B9") (pintype "passive"))
      (node (ref "J11") (pin "A9/B4") (pinfunction "VBUS_A9/B4") (pintype "passive"))
      (node (ref "J12") (pin "1") (pinfunction "1_1") (pintype "passive"))
    )
    (net (code "126") (name "U5V") (class "Default")
      (node (ref "J4") (pin "8") (pinfunction "8_8") (pintype "passive"))
    )
    (net (code "127") (name "VBAT") (class "Default")
      (node (ref "J1") (pin "33") (pinfunction "33_33") (pintype "passive"))
    )
    (net (code "128") (name "VDD") (class "Default")
      (node (ref "J1") (pin "5") (pinfunction "5_5") (pintype "passive"))
    )
    (net (code "129") (name "VIN") (class "Default")
      (node (ref "J1") (pin "24") (pinfunction "24_24") (pintype "passive"))
    )
    (net (code "130") (name "unconnected-(J1-Pad4)") (class "Default")
      (node (ref "J1") (pin "4") (pinfunction "4_4") (pintype "passive"))
    )
    (net (code "131") (name "unconnected-(J1-Pad10)") (class "Default")
      (node (ref "J1") (pin "10") (pinfunction "10_10") (pintype "passive"))
    )
    (net (code "132") (name "unconnected-(J1-Pad25)") (class "Default")
      (node (ref "J1") (pin "25") (pinfunction "25_25") (pintype "passive"))
    )
    (net (code "133") (name "unconnected-(J1-Pad26)") (class "Default")
      (node (ref "J1") (pin "26") (pinfunction "26_26") (pintype "passive"))
    )
    (net (code "134") (name "unconnected-(J1-Pad27)") (class "Default")
      (node (ref "J1") (pin "27") (pinfunction "27_27") (pintype "passive"))
    )
    (net (code "135") (name "unconnected-(J1-Pad29)") (class "Default")
      (node (ref "J1") (pin "29") (pinfunction "29_29") (pintype "passive"))
    )
    (net (code "136") (name "unconnected-(J2-Pad35)") (class "Default")
      (node (ref "J2") (pin "35") (pinfunction "35_35") (pintype "passive"))
    )
    (net (code "137") (name "unconnected-(J2-Pad36)") (class "Default")
      (node (ref "J2") (pin "36") (pinfunction "36_36") (pintype "passive"))
    )
    (net (code "138") (name "unconnected-(J5-Pad35)") (class "Default")
      (node (ref "J5") (pin "35") (pinfunction "35_35") (pintype "passive"))
    )
    (net (code "139") (name "unconnected-(J5-Pad36)") (class "Default")
      (node (ref "J5") (pin "36") (pinfunction "36_36") (pintype "passive"))
    )
    (net (code "140") (name "unconnected-(J11-SBU1-PadA8)") (class "Default")
      (node (ref "J11") (pin "A8") (pinfunction "SBU1_A8") (pintype "passive"))
    )
    (net (code "141") (name "unconnected-(J11-SBU2-PadB8)") (class "Default")
      (node (ref "J11") (pin "B8") (pinfunction "SBU2_B8") (pintype "passive"))
    )
    (net (code "142") (name "unconnected-(P2-Pad3)") (class "Default")
      (node (ref "P2") (pin "3") (pinfunction "3_3") (pintype "passive"))
    )
    (net (code "143") (name "unconnected-(P2-Pad4)") (class "Default")
      (node (ref "P2") (pin "4") (pinfunction "4_4") (pintype "passive"))
    )
    (net (code "144") (name "unconnected-(P2-Pad5)") (class "Default")
      (node (ref "P2") (pin "5") (pinfunction "5_5") (pintype "passive"))
    )
    (net (code "145") (name "unconnected-(P2-Pad6)") (class "Default")
      (node (ref "P2") (pin "6") (pinfunction "6_6") (pintype "passive"))
    )
    (net (code "146") (name "unconnected-(P2-Pad7)") (class "Default")
      (node (ref "P2") (pin "7") (pinfunction "7_7") (pintype "passive"))
    )
    (net (code "147") (name "unconnected-(P2-Pad8)") (class "Default")
      (node (ref "P2") (pin "8") (pinfunction "8_8") (pintype "passive"))
    )
    (net (code "148") (name "unconnected-(P2-Pad11)") (class "Default")
      (node (ref "P2") (pin "11") (pinfunction "11_11") (pintype "passive"))
    )
    (net (code "149") (name "unconnected-(P2-Pad12)") (class "Default")
      (node (ref "P2") (pin "12") (pinfunction "12_12") (pintype "passive"))
    )
    (net (code "150") (name "unconnected-(P2-Pad13)") (class "Default")
      (node (ref "P2") (pin "13") (pinfunction "13_13") (pintype "passive"))
    )
    (net (code "151") (name "unconnected-(P2-Pad14)") (class "Default")
      (node (ref "P2") (pin "14") (pinfunction "14_14") (pintype "passive"))
    )
    (net (code "152") (name "unconnected-(P2-Pad15)") (class "Default")
      (node (ref "P2") (pin "15") (pinfunction "15_15") (pintype "passive"))
    )
    (net (code "153") (name "unconnected-(P2-Pad16)") (class "Default")
      (node (ref "P2") (pin "16") (pinfunction "16_16") (pintype "passive"))
    )
    (net (code "154") (name "unconnected-(P2-Pad17)") (class "Default")
      (node (ref "P2") (pin "17") (pinfunction "17_17") (pintype "passive"))
    )
    (net (code "155") (name "unconnected-(P2-Pad18)") (class "Default")
      (node (ref "P2") (pin "18") (pinfunction "18_18") (pintype "passive"))
    )
    (net (code "156") (name "unconnected-(P2-Pad19)") (class "Default")
      (node (ref "P2") (pin "19") (pinfunction "19_19") (pintype "passive"))
    )
    (net (code "157") (name "unconnected-(P2-Pad21)") (class "Default")
      (node (ref "P2") (pin "21") (pinfunction "21_21") (pintype "passive"))
    )
    (net (code "158") (name "unconnected-(P2-Pad22)") (class "Default")
      (node (ref "P2") (pin "22") (pinfunction "22_22") (pintype "passive"))
    )
    (net (code "159") (name "unconnected-(P2-Pad23)") (class "Default")
      (node (ref "P2") (pin "23") (pinfunction "23_23") (pintype "passive"))
    )
    (net (code "160") (name "unconnected-(P2-Pad24)") (class "Default")
      (node (ref "P2") (pin "24") (pinfunction "24_24") (pintype "passive"))
    )
    (net (code "161") (name "unconnected-(P2-Pad25)") (class "Default")
      (node (ref "P2") (pin "25") (pinfunction "25_25") (pintype "passive"))
    )
    (net (code "162") (name "unconnected-(P2-Pad26)") (class "Default")
      (node (ref "P2") (pin "26") (pinfunction "26_26") (pintype "passive"))
    )
    (net (code "163") (name "unconnected-(P2-Pad27)") (class "Default")
      (node (ref "P2") (pin "27") (pinfunction "27_27") (pintype "passive"))
    )
    (net (code "164") (name "unconnected-(P2-Pad28)") (class "Default")
      (node (ref "P2") (pin "28") (pinfunction "28_28") (pintype "passive"))
    )
    (net (code "165") (name "unconnected-(P2-Pad29)") (class "Default")
      (node (ref "P2") (pin "29") (pinfunction "29_29") (pintype "passive"))
    )
    (net (code "166") (name "unconnected-(P2-Pad30)") (class "Default")
      (node (ref "P2") (pin "30") (pinfunction "30_30") (pintype "passive"))
    )
    (net (code "167") (name "unconnected-(P2-Pad31)") (class "Default")
      (node (ref "P2") (pin "31") (pinfunction "31_31") (pintype "passive"))
    )
    (net (code "168") (name "unconnected-(P2-Pad33)") (class "Default")
      (node (ref "P2") (pin "33") (pinfunction "33_33") (pintype "passive"))
    )
    (net (code "169") (name "unconnected-(P2-Pad34)") (class "Default")
      (node (ref "P2") (pin "34") (pinfunction "34_34") (pintype "passive"))
    )
    (net (code "170") (name "unconnected-(P2-Pad35)") (class "Default")
      (node (ref "P2") (pin "35") (pinfunction "35_35") (pintype "passive"))
    )
    (net (code "171") (name "unconnected-(P3-Pad1)") (class "Default")
      (node (ref "P3") (pin "1") (pinfunction "1_1") (pintype "passive"))
    )
    (net (code "172") (name "unconnected-(P3-Pad2)") (class "Default")
      (node (ref "P3") (pin "2") (pinfunction "2_2") (pintype "passive"))
    )
    (net (code "173") (name "unconnected-(P3-Pad3)") (class "Default")
      (node (ref "P3") (pin "3") (pinfunction "3_3") (pintype "passive"))
    )
    (net (code "174") (name "unconnected-(P3-Pad4)") (class "Default")
      (node (ref "P3") (pin "4") (pinfunction "4_4") (pintype "passive"))
    )
    (net (code "175") (name "unconnected-(P3-Pad5)") (class "Default")
      (node (ref "P3") (pin "5") (pinfunction "5_5") (pintype "passive"))
    )
    (net (code "176") (name "unconnected-(P3-Pad6)") (class "Default")
      (node (ref "P3") (pin "6") (pinfunction "6_6") (pintype "passive"))
    )
    (net (code "177") (name "unconnected-(P3-Pad7)") (class "Default")
      (node (ref "P3") (pin "7") (pinfunction "7_7") (pintype "passive"))
    )
    (net (code "178") (name "unconnected-(P3-Pad9)") (class "Default")
      (node (ref "P3") (pin "9") (pinfunction "9_9") (pintype "passive"))
    )
    (net (code "179") (name "unconnected-(P3-Pad10)") (class "Default")
      (node (ref "P3") (pin "10") (pinfunction "10_10") (pintype "passive"))
    )
    (net (code "180") (name "unconnected-(P3-Pad11)") (class "Default")
      (node (ref "P3") (pin "11") (pinfunction "11_11") (pintype "passive"))
    )
    (net (code "181") (name "unconnected-(P3-Pad12)") (class "Default")
      (node (ref "P3") (pin "12") (pinfunction "12_12") (pintype "passive"))
    )
    (net (code "182") (name "unconnected-(P3-Pad13)") (class "Default")
      (node (ref "P3") (pin "13") (pinfunction "13_13") (pintype "passive"))
    )
    (net (code "183") (name "unconnected-(P3-Pad14)") (class "Default")
      (node (ref "P3") (pin "14") (pinfunction "14_14") (pintype "passive"))
    )
    (net (code "184") (name "unconnected-(P3-Pad15)") (class "Default")
      (node (ref "P3") (pin "15") (pinfunction "15_15") (pintype "passive"))
    )
    (net (code "185") (name "unconnected-(P3-Pad16)") (class "Default")
      (node (ref "P3") (pin "16") (pinfunction "16_16") (pintype "passive"))
    )
    (net (code "186") (name "unconnected-(P3-Pad17)") (class "Default")
      (node (ref "P3") (pin "17") (pinfunction "17_17") (pintype "passive"))
    )
    (net (code "187") (name "unconnected-(P3-Pad21)") (class "Default")
      (node (ref "P3") (pin "21") (pinfunction "21_21") (pintype "passive"))
    )
    (net (code "188") (name "unconnected-(P3-Pad23)") (class "Default")
      (node (ref "P3") (pin "23") (pinfunction "23_23") (pintype "passive"))
    )
    (net (code "189") (name "unconnected-(P3-Pad24)") (class "Default")
      (node (ref "P3") (pin "24") (pinfunction "24_24") (pintype "passive"))
    )
    (net (code "190") (name "unconnected-(P3-Pad25)") (class "Default")
      (node (ref "P3") (pin "25") (pinfunction "25_25") (pintype "passive"))
    )
    (net (code "191") (name "unconnected-(P3-Pad26)") (class "Default")
      (node (ref "P3") (pin "26") (pinfunction "26_26") (pintype "passive"))
    )
    (net (code "192") (name "unconnected-(P3-Pad27)") (class "Default")
      (node (ref "P3") (pin "27") (pinfunction "27_27") (pintype "passive"))
    )
    (net (code "193") (name "unconnected-(P3-Pad28)") (class "Default")
      (node (ref "P3") (pin "28") (pinfunction "28_28") (pintype "passive"))
    )
    (net (code "194") (name "unconnected-(P3-Pad29)") (class "Default")
      (node (ref "P3") (pin "29") (pinfunction "29_29") (pintype "passive"))
    )
    (net (code "195") (name "unconnected-(P3-Pad30)") (class "Default")
      (node (ref "P3") (pin "30") (pinfunction "30_30") (pintype "passive"))
    )
    (net (code "196") (name "unconnected-(P3-Pad31)") (class "Default")
      (node (ref "P3") (pin "31") (pinfunction "31_31") (pintype "passive"))
    )
    (net (code "197") (name "unconnected-(P3-Pad32)") (class "Default")
      (node (ref "P3") (pin "32") (pinfunction "32_32") (pintype "passive"))
    )
    (net (code "198") (name "unconnected-(P3-Pad33)") (class "Default")
      (node (ref "P3") (pin "33") (pinfunction "33_33") (pintype "passive"))
    )
    (net (code "199") (name "unconnected-(P3-Pad34)") (class "Default")
      (node (ref "P3") (pin "34") (pinfunction "34_34") (pintype "passive"))
    )
    (net (code "200") (name "unconnected-(P3-Pad35)") (class "Default")
      (node (ref "P3") (pin "35") (pinfunction "35_35") (pintype "passive"))
    )
    (net (code "201") (name "unconnected-(P3-Pad36)") (class "Default")
      (node (ref "P3") (pin "36") (pinfunction "36_36") (pintype "passive"))
    )
    (net (code "202") (name "unconnected-(P4-Pad1)") (class "Default")
      (node (ref "P4") (pin "1") (pinfunction "1_1") (pintype "passive"))
    )
    (net (code "203") (name "unconnected-(P4-Pad5)") (class "Default")
      (node (ref "P4") (pin "5") (pinfunction "5_5") (pintype "passive"))
    )
    (net (code "204") (name "unconnected-(P4-Pad6)") (class "Default")
      (node (ref "P4") (pin "6") (pinfunction "6_6") (pintype "passive"))
    )
    (net (code "205") (name "unconnected-(P4-Pad7)") (class "Default")
      (node (ref "P4") (pin "7") (pinfunction "7_7") (pintype "passive"))
    )
    (net (code "206") (name "unconnected-(P4-Pad9)") (class "Default")
      (node (ref "P4") (pin "9") (pinfunction "9_9") (pintype "passive"))
    )
    (net (code "207") (name "unconnected-(P4-Pad25)") (class "Default")
      (node (ref "P4") (pin "25") (pinfunction "25_25") (pintype "passive"))
    )
    (net (code "208") (name "unconnected-(P4-Pad26)") (class "Default")
      (node (ref "P4") (pin "26") (pinfunction "26_26") (pintype "passive"))
    )
    (net (code "209") (name "unconnected-(P4-Pad28)") (class "Default")
      (node (ref "P4") (pin "28") (pinfunction "28_28") (pintype "passive"))
    )
    (net (code "210") (name "unconnected-(P4-Pad30)") (class "Default")
      (node (ref "P4") (pin "30") (pinfunction "30_30") (pintype "passive"))
    )
    (net (code "211") (name "unconnected-(P4-Pad31)") (class "Default")
      (node (ref "P4") (pin "31") (pinfunction "31_31") (pintype "passive"))
    )
    (net (code "212") (name "unconnected-(P4-Pad32)") (class "Default")
      (node (ref "P4") (pin "32") (pinfunction "32_32") (pintype "passive"))
    )
    (net (code "213") (name "unconnected-(P4-Pad33)") (class "Default")
      (node (ref "P4") (pin "33") (pinfunction "33_33") (pintype "passive"))
    )
    (net (code "214") (name "unconnected-(P4-Pad34)") (class "Default")
      (node (ref "P4") (pin "34") (pinfunction "34_34") (pintype "passive"))
    )
    (net (code "215") (name "unconnected-(P4-Pad35)") (class "Default")
      (node (ref "P4") (pin "35") (pinfunction "35_35") (pintype "passive"))
    )
    (net (code "216") (name "unconnected-(P4-Pad36)") (class "Default")
      (node (ref "P4") (pin "36") (pinfunction "36_36") (pintype "passive"))
    )
    (net (code "217") (name "unconnected-(P5-Pad1)") (class "Default")
      (node (ref "P5") (pin "1") (pinfunction "1_1") (pintype "passive"))
    )
    (net (code "218") (name "unconnected-(P5-Pad2)") (class "Default")
      (node (ref "P5") (pin "2") (pinfunction "2_2") (pintype "passive"))
    )
    (net (code "219") (name "unconnected-(P5-Pad4)") (class "Default")
      (node (ref "P5") (pin "4") (pinfunction "4_4") (pintype "passive"))
    )
    (net (code "220") (name "unconnected-(P5-Pad6)") (class "Default")
      (node (ref "P5") (pin "6") (pinfunction "6_6") (pintype "passive"))
    )
    (net (code "221") (name "unconnected-(P5-Pad7)") (class "Default")
      (node (ref "P5") (pin "7") (pinfunction "7_7") (pintype "passive"))
    )
    (net (code "222") (name "unconnected-(P5-Pad8)") (class "Default")
      (node (ref "P5") (pin "8") (pinfunction "8_8") (pintype "passive"))
    )
    (net (code "223") (name "unconnected-(P5-Pad18)") (class "Default")
      (node (ref "P5") (pin "18") (pinfunction "18_18") (pintype "passive"))
    )
    (net (code "224") (name "unconnected-(P5-Pad20)") (class "Default")
      (node (ref "P5") (pin "20") (pinfunction "20_20") (pintype "passive"))
    )
    (net (code "225") (name "unconnected-(P5-Pad22)") (class "Default")
      (node (ref "P5") (pin "22") (pinfunction "22_22") (pintype "passive"))
    )
    (net (code "226") (name "unconnected-(P5-Pad23)") (class "Default")
      (node (ref "P5") (pin "23") (pinfunction "23_23") (pintype "passive"))
    )
    (net (code "227") (name "unconnected-(P5-Pad25)") (class "Default")
      (node (ref "P5") (pin "25") (pinfunction "25_25") (pintype "passive"))
    )
    (net (code "228") (name "unconnected-(P5-Pad26)") (class "Default")
      (node (ref "P5") (pin "26") (pinfunction "26_26") (pintype "passive"))
    )
    (net (code "229") (name "unconnected-(P5-Pad27)") (class "Default")
      (node (ref "P5") (pin "27") (pinfunction "27_27") (pintype "passive"))
    )
    (net (code "230") (name "unconnected-(P5-Pad28)") (class "Default")
      (node (ref "P5") (pin "28") (pinfunction "28_28") (pintype "passive"))
    )
    (net (code "231") (name "unconnected-(P5-Pad29)") (class "Default")
      (node (ref "P5") (pin "29") (pinfunction "29_29") (pintype "passive"))
    )
    (net (code "232") (name "unconnected-(P5-Pad30)") (class "Default")
      (node (ref "P5") (pin "30") (pinfunction "30_30") (pintype "passive"))
    )
    (net (code "233") (name "unconnected-(P5-Pad31)") (class "Default")
      (node (ref "P5") (pin "31") (pinfunction "31_31") (pintype "passive"))
    )
    (net (code "234") (name "unconnected-(P5-Pad32)") (class "Default")
      (node (ref "P5") (pin "32") (pinfunction "32_32") (pintype "passive"))
    )
    (net (code "235") (name "unconnected-(P5-Pad34)") (class "Default")
      (node (ref "P5") (pin "34") (pinfunction "34_34") (pintype "passive"))
    )
    (net (code "236") (name "unconnected-(P5-Pad35)") (class "Default")
      (node (ref "P5") (pin "35") (pinfunction "35_35") (pintype "passive"))
    )
    (net (code "237") (name "unconnected-(P5-Pad36)") (class "Default")
      (node (ref "P5") (pin "36") (pinfunction "36_36") (pintype "passive"))
    )
    (net (code "238") (name "unconnected-(U7A-+3V3-PadCN11_16)") (class "Default")
      (node (ref "U7") (pin "CN11_16") (pinfunction "+3V3_CN11_16") (pintype "power_in"))
    )
    (net (code "239") (name "unconnected-(U7A-+5V-PadCN11_18)") (class "Default")
      (node (ref "U7") (pin "CN11_18") (pinfunction "+5V_CN11_18") (pintype "power_in"))
    )
    (net (code "240") (name "unconnected-(U7A-BOOT0-PadCN11_7)") (class "Default")
      (node (ref "U7") (pin "CN11_7") (pinfunction "BOOT0_CN11_7") (pintype "bidirectional"))
    )
    (net (code "241") (name "unconnected-(U7A-E5V-PadCN11_6)") (class "Default")
      (node (ref "U7") (pin "CN11_6") (pinfunction "E5V_CN11_6") (pintype "power_in"))
    )
    (net (code "242") (name "unconnected-(U7A-GND_CN11-PadCN11_8)") (class "Default")
      (node (ref "U7") (pin "CN11_8") (pinfunction "GND_CN11_CN11_8") (pintype "power_in"))
    )
    (net (code "243") (name "unconnected-(U7A-GND_CN11-PadCN11_19)") (class "Default")
      (node (ref "U7") (pin "CN11_19") (pinfunction "GND_CN11_CN11_19") (pintype "power_in"))
    )
    (net (code "244") (name "unconnected-(U7A-GND_CN11-PadCN11_20)") (class "Default")
      (node (ref "U7") (pin "CN11_20") (pinfunction "GND_CN11_CN11_20") (pintype "power_in"))
    )
    (net (code "245") (name "unconnected-(U7A-GND_CN11-PadCN11_22)") (class "Default")
      (node (ref "U7") (pin "CN11_22") (pinfunction "GND_CN11_CN11_22") (pintype "power_in"))
    )
    (net (code "246") (name "unconnected-(U7A-GND_CN11-PadCN11_49)") (class "Default")
      (node (ref "U7") (pin "CN11_49") (pinfunction "GND_CN11_CN11_49") (pintype "power_in"))
    )
    (net (code "247") (name "unconnected-(U7A-GND_CN11-PadCN11_60)") (class "Default")
      (node (ref "U7") (pin "CN11_60") (pinfunction "GND_CN11_CN11_60") (pintype "power_in"))
    )
    (net (code "248") (name "unconnected-(U7A-GND_CN11-PadCN11_71)") (class "Default")
      (node (ref "U7") (pin "CN11_71") (pinfunction "GND_CN11_CN11_71") (pintype "power_in"))
    )
    (net (code "249") (name "unconnected-(U7A-GND_CN11-PadCN11_72)") (class "Default")
      (node (ref "U7") (pin "CN11_72") (pinfunction "GND_CN11_CN11_72") (pintype "power_in"))
    )
    (net (code "250") (name "unconnected-(U7A-IOREF-PadCN11_12)") (class "Default")
      (node (ref "U7") (pin "CN11_12") (pinfunction "IOREF_CN11_12") (pintype "bidirectional"))
    )
    (net (code "251") (name "unconnected-(U7A-NC-PadCN11_10)") (class "Default")
      (node (ref "U7") (pin "CN11_10") (pinfunction "NC_CN11_10") (pintype "passive"))
    )
    (net (code "252") (name "unconnected-(U7A-NC-PadCN11_26)") (class "Default")
      (node (ref "U7") (pin "CN11_26") (pinfunction "NC_CN11_26") (pintype "passive"))
    )
    (net (code "253") (name "unconnected-(U7A-NC-PadCN11_67)") (class "Default")
      (node (ref "U7") (pin "CN11_67") (pinfunction "NC_CN11_67") (pintype "passive"))
    )
    (net (code "254") (name "unconnected-(U7A-PA0-PadCN11_28)") (class "Default")
      (node (ref "U7") (pin "CN11_28") (pinfunction "PA0_CN11_28") (pintype "bidirectional"))
    )
    (net (code "255") (name "unconnected-(U7A-PA1-PadCN11_30)") (class "Default")
      (node (ref "U7") (pin "CN11_30") (pinfunction "PA1_CN11_30") (pintype "bidirectional"))
    )
    (net (code "256") (name "unconnected-(U7A-PA4-PadCN11_32)") (class "Default")
      (node (ref "U7") (pin "CN11_32") (pinfunction "PA4_CN11_32") (pintype "bidirectional"))
    )
    (net (code "257") (name "unconnected-(U7A-PA13-PadCN11_13)") (class "Default")
      (node (ref "U7") (pin "CN11_13") (pinfunction "PA13_CN11_13") (pintype "bidirectional"))
    )
    (net (code "258") (name "unconnected-(U7A-PA14-PadCN11_15)") (class "Default")
      (node (ref "U7") (pin "CN11_15") (pinfunction "PA14_CN11_15") (pintype "bidirectional"))
    )
    (net (code "259") (name "unconnected-(U7A-PA15-PadCN11_17)") (class "Default")
      (node (ref "U7") (pin "CN11_17") (pinfunction "PA15_CN11_17") (pintype "bidirectional"))
    )
    (net (code "260") (name "unconnected-(U7A-PB0-PadCN11_34)") (class "Default")
      (node (ref "U7") (pin "CN11_34") (pinfunction "PB0_CN11_34") (pintype "bidirectional"))
    )
    (net (code "261") (name "unconnected-(U7A-PB7-PadCN11_21)") (class "Default")
      (node (ref "U7") (pin "CN11_21") (pinfunction "PB7_CN11_21") (pintype "bidirectional"))
    )
    (net (code "262") (name "unconnected-(U7A-PC0-PadCN11_38)") (class "Default")
      (node (ref "U7") (pin "CN11_38") (pinfunction "PC0_CN11_38") (pintype "bidirectional"))
    )
    (net (code "263") (name "unconnected-(U7A-PC1-PadCN11_36)") (class "Default")
      (node (ref "U7") (pin "CN11_36") (pinfunction "PC1_CN11_36") (pintype "bidirectional"))
    )
    (net (code "264") (name "unconnected-(U7A-PC2-PadCN11_35)") (class "Default")
      (node (ref "U7") (pin "CN11_35") (pinfunction "PC2_CN11_35") (pintype "bidirectional"))
    )
    (net (code "265") (name "unconnected-(U7A-PC3-PadCN11_37)") (class "Default")
      (node (ref "U7") (pin "CN11_37") (pinfunction "PC3_CN11_37") (pintype "bidirectional"))
    )
    (net (code "266") (name "unconnected-(U7A-PC10-PadCN11_1)") (class "Default")
      (node (ref "U7") (pin "CN11_1") (pinfunction "PC10_CN11_1") (pintype "bidirectional"))
    )
    (net (code "267") (name "unconnected-(U7A-PC11-PadCN11_2)") (class "Default")
      (node (ref "U7") (pin "CN11_2") (pinfunction "PC11_CN11_2") (pintype "bidirectional"))
    )
    (net (code "268") (name "unconnected-(U7A-PC12-PadCN11_3)") (class "Default")
      (node (ref "U7") (pin "CN11_3") (pinfunction "PC12_CN11_3") (pintype "bidirectional"))
    )
    (net (code "269") (name "unconnected-(U7A-PC13-PadCN11_23)") (class "Default")
      (node (ref "U7") (pin "CN11_23") (pinfunction "PC13_CN11_23") (pintype "bidirectional"))
    )
    (net (code "270") (name "unconnected-(U7A-PC14-PadCN11_25)") (class "Default")
      (node (ref "U7") (pin "CN11_25") (pinfunction "PC14_CN11_25") (pintype "bidirectional"))
    )
    (net (code "271") (name "unconnected-(U7A-PC15-PadCN11_27)") (class "Default")
      (node (ref "U7") (pin "CN11_27") (pinfunction "PC15_CN11_27") (pintype "bidirectional"))
    )
    (net (code "272") (name "unconnected-(U7A-PD0-PadCN11_57)") (class "Default")
      (node (ref "U7") (pin "CN11_57") (pinfunction "PD0_CN11_57") (pintype "bidirectional"))
    )
    (net (code "273") (name "unconnected-(U7A-PD1-PadCN11_55)") (class "Default")
      (node (ref "U7") (pin "CN11_55") (pinfunction "PD1_CN11_55") (pintype "bidirectional"))
    )
    (net (code "274") (name "unconnected-(U7A-PD2-PadCN11_4)") (class "Default")
      (node (ref "U7") (pin "CN11_4") (pinfunction "PD2_CN11_4") (pintype "bidirectional"))
    )
    (net (code "275") (name "unconnected-(U7A-PD3-PadCN11_40)") (class "Default")
      (node (ref "U7") (pin "CN11_40") (pinfunction "PD3_CN11_40") (pintype "bidirectional"))
    )
    (net (code "276") (name "unconnected-(U7A-PD4-PadCN11_39)") (class "Default")
      (node (ref "U7") (pin "CN11_39") (pinfunction "PD4_CN11_39") (pintype "bidirectional"))
    )
    (net (code "277") (name "unconnected-(U7A-PD5-PadCN11_41)") (class "Default")
      (node (ref "U7") (pin "CN11_41") (pinfunction "PD5_CN11_41") (pintype "bidirectional"))
    )
    (net (code "278") (name "unconnected-(U7A-PD6-PadCN11_43)") (class "Default")
      (node (ref "U7") (pin "CN11_43") (pinfunction "PD6_CN11_43") (pintype "bidirectional"))
    )
    (net (code "279") (name "unconnected-(U7A-PD7-PadCN11_45)") (class "Default")
      (node (ref "U7") (pin "CN11_45") (pinfunction "PD7_CN11_45") (pintype "bidirectional"))
    )
    (net (code "280") (name "unconnected-(U7A-PD9-PadCN11_69)") (class "Default")
      (node (ref "U7") (pin "CN11_69") (pinfunction "PD9_CN11_69") (pintype "bidirectional"))
    )
    (net (code "281") (name "unconnected-(U7A-PE1-PadCN11_61)") (class "Default")
      (node (ref "U7") (pin "CN11_61") (pinfunction "PE1_CN11_61") (pintype "bidirectional"))
    )
    (net (code "282") (name "unconnected-(U7A-PE2-PadCN11_46)") (class "Default")
      (node (ref "U7") (pin "CN11_46") (pinfunction "PE2_CN11_46") (pintype "bidirectional"))
    )
    (net (code "283") (name "unconnected-(U7A-PE3-PadCN11_47)") (class "Default")
      (node (ref "U7") (pin "CN11_47") (pinfunction "PE3_CN11_47") (pintype "bidirectional"))
    )
    (net (code "284") (name "unconnected-(U7A-PE4-PadCN11_48)") (class "Default")
      (node (ref "U7") (pin "CN11_48") (pinfunction "PE4_CN11_48") (pintype "bidirectional"))
    )
    (net (code "285") (name "unconnected-(U7A-PE5-PadCN11_50)") (class "Default")
      (node (ref "U7") (pin "CN11_50") (pinfunction "PE5_CN11_50") (pintype "bidirectional"))
    )
    (net (code "286") (name "unconnected-(U7A-PE6-PadCN11_62)") (class "Default")
      (node (ref "U7") (pin "CN11_62") (pinfunction "PE6_CN11_62") (pintype "bidirectional"))
    )
    (net (code "287") (name "unconnected-(U7A-PF0-PadCN11_53)") (class "Default")
      (node (ref "U7") (pin "CN11_53") (pinfunction "PF0_CN11_53") (pintype "bidirectional"))
    )
    (net (code "288") (name "unconnected-(U7A-PF1-PadCN11_51)") (class "Default")
      (node (ref "U7") (pin "CN11_51") (pinfunction "PF1_CN11_51") (pintype "bidirectional"))
    )
    (net (code "289") (name "unconnected-(U7A-PF2-PadCN11_52)") (class "Default")
      (node (ref "U7") (pin "CN11_52") (pinfunction "PF2_CN11_52") (pintype "bidirectional"))
    )
    (net (code "290") (name "unconnected-(U7A-PF6-PadCN11_9)") (class "Default")
      (node (ref "U7") (pin "CN11_9") (pinfunction "PF6_CN11_9") (pintype "bidirectional"))
    )
    (net (code "291") (name "unconnected-(U7A-PF7-PadCN11_11)") (class "Default")
      (node (ref "U7") (pin "CN11_11") (pinfunction "PF7_CN11_11") (pintype "bidirectional"))
    )
    (net (code "292") (name "unconnected-(U7A-PF8-PadCN11_54)") (class "Default")
      (node (ref "U7") (pin "CN11_54") (pinfunction "PF8_CN11_54") (pintype "bidirectional"))
    )
    (net (code "293") (name "unconnected-(U7A-PF9-PadCN11_56)") (class "Default")
      (node (ref "U7") (pin "CN11_56") (pinfunction "PF9_CN11_56") (pintype "bidirectional"))
    )
    (net (code "294") (name "unconnected-(U7A-PG0-PadCN11_59)") (class "Default")
      (node (ref "U7") (pin "CN11_59") (pinfunction "PG0_CN11_59") (pintype "bidirectional"))
    )
    (net (code "295") (name "unconnected-(U7A-PG1-PadCN11_58)") (class "Default")
      (node (ref "U7") (pin "CN11_58") (pinfunction "PG1_CN11_58") (pintype "bidirectional"))
    )
    (net (code "296") (name "unconnected-(U7A-PG2-PadCN11_42)") (class "Default")
      (node (ref "U7") (pin "CN11_42") (pinfunction "PG2_CN11_42") (pintype "bidirectional"))
    )
    (net (code "297") (name "unconnected-(U7A-PG3-PadCN11_44)") (class "Default")
      (node (ref "U7") (pin "CN11_44") (pinfunction "PG3_CN11_44") (pintype "bidirectional"))
    )
    (net (code "298") (name "unconnected-(U7A-PG9-PadCN11_63)") (class "Default")
      (node (ref "U7") (pin "CN11_63") (pinfunction "PG9_CN11_63") (pintype "bidirectional"))
    )
    (net (code "299") (name "unconnected-(U7A-PG10-PadCN11_66)") (class "Default")
      (node (ref "U7") (pin "CN11_66") (pinfunction "PG10_CN11_66") (pintype "bidirectional"))
    )
    (net (code "300") (name "unconnected-(U7A-PG11-PadCN11_70)") (class "Default")
      (node (ref "U7") (pin "CN11_70") (pinfunction "PG11_CN11_70") (pintype "bidirectional"))
    )
    (net (code "301") (name "unconnected-(U7A-PG12-PadCN11_65)") (class "Default")
      (node (ref "U7") (pin "CN11_65") (pinfunction "PG12_CN11_65") (pintype "bidirectional"))
    )
    (net (code "302") (name "unconnected-(U7A-PG13-PadCN11_68)") (class "Default")
      (node (ref "U7") (pin "CN11_68") (pinfunction "PG13_CN11_68") (pintype "bidirectional"))
    )
    (net (code "303") (name "unconnected-(U7A-PG15-PadCN11_64)") (class "Default")
      (node (ref "U7") (pin "CN11_64") (pinfunction "PG15_CN11_64") (pintype "bidirectional"))
    )
    (net (code "304") (name "unconnected-(U7A-PH0-PadCN11_29)") (class "Default")
      (node (ref "U7") (pin "CN11_29") (pinfunction "PH0_CN11_29") (pintype "bidirectional"))
    )
    (net (code "305") (name "unconnected-(U7A-PH1-PadCN11_31)") (class "Default")
      (node (ref "U7") (pin "CN11_31") (pinfunction "PH1_CN11_31") (pintype "bidirectional"))
    )
    (net (code "306") (name "unconnected-(U7A-RESET-PadCN11_14)") (class "Default")
      (node (ref "U7") (pin "CN11_14") (pinfunction "RESET_CN11_14") (pintype "bidirectional"))
    )
    (net (code "307") (name "unconnected-(U7A-VBAT-PadCN11_33)") (class "Default")
      (node (ref "U7") (pin "CN11_33") (pinfunction "VBAT_CN11_33") (pintype "power_in"))
    )
    (net (code "308") (name "unconnected-(U7A-VDD-PadCN11_5)") (class "Default")
      (node (ref "U7") (pin "CN11_5") (pinfunction "VDD_CN11_5") (pintype "power_in"))
    )
    (net (code "309") (name "unconnected-(U7A-VIN-PadCN11_24)") (class "Default")
      (node (ref "U7") (pin "CN11_24") (pinfunction "VIN_CN11_24") (pintype "power_in"))
    )
    (net (code "310") (name "unconnected-(U7B-AGND_CN12-PadCN12_32)") (class "Default")
      (node (ref "U7") (pin "CN12_32") (pinfunction "AGND_CN12_CN12_32") (pintype "power_in"))
    )
    (net (code "311") (name "unconnected-(U7B-AVDD_CN12-PadCN12_7)") (class "Default")
      (node (ref "U7") (pin "CN12_7") (pinfunction "AVDD_CN12_CN12_7") (pintype "power_in"))
    )
    (net (code "312") (name "unconnected-(U7B-GND_CN12-PadCN12_9)") (class "Default")
      (node (ref "U7") (pin "CN12_9") (pinfunction "GND_CN12_CN12_9") (pintype "power_in"))
    )
    (net (code "313") (name "unconnected-(U7B-GND_CN12-PadCN12_20)") (class "Default")
      (node (ref "U7") (pin "CN12_20") (pinfunction "GND_CN12_CN12_20") (pintype "power_in"))
    )
    (net (code "314") (name "unconnected-(U7B-GND_CN12-PadCN12_39)") (class "Default")
      (node (ref "U7") (pin "CN12_39") (pinfunction "GND_CN12_CN12_39") (pintype "power_in"))
    )
    (net (code "315") (name "unconnected-(U7B-GND_CN12-PadCN12_54)") (class "Default")
      (node (ref "U7") (pin "CN12_54") (pinfunction "GND_CN12_CN12_54") (pintype "power_in"))
    )
    (net (code "316") (name "unconnected-(U7B-GND_CN12-PadCN12_63)") (class "Default")
      (node (ref "U7") (pin "CN12_63") (pinfunction "GND_CN12_CN12_63") (pintype "power_in"))
    )
    (net (code "317") (name "unconnected-(U7B-GND_CN12-PadCN12_71)") (class "Default")
      (node (ref "U7") (pin "CN12_71") (pinfunction "GND_CN12_CN12_71") (pintype "power_in"))
    )
    (net (code "318") (name "unconnected-(U7B-GND_CN12-PadCN12_72)") (class "Default")
      (node (ref "U7") (pin "CN12_72") (pinfunction "GND_CN12_CN12_72") (pintype "power_in"))
    )
    (net (code "319") (name "unconnected-(U7B-PA2-PadCN12_35)") (class "Default")
      (node (ref "U7") (pin "CN12_35") (pinfunction "PA2_CN12_35") (pintype "bidirectional"))
    )
    (net (code "320") (name "unconnected-(U7B-PA3-PadCN12_37)") (class "Default")
      (node (ref "U7") (pin "CN12_37") (pinfunction "PA3_CN12_37") (pintype "bidirectional"))
    )
    (net (code "321") (name "unconnected-(U7B-PA5-PadCN12_11)") (class "Default")
      (node (ref "U7") (pin "CN12_11") (pinfunction "PA5_CN12_11") (pintype "bidirectional"))
    )
    (net (code "322") (name "unconnected-(U7B-PA6-PadCN12_13)") (class "Default")
      (node (ref "U7") (pin "CN12_13") (pinfunction "PA6_CN12_13") (pintype "bidirectional"))
    )
    (net (code "323") (name "unconnected-(U7B-PA7-PadCN12_15)") (class "Default")
      (node (ref "U7") (pin "CN12_15") (pinfunction "PA7_CN12_15") (pintype "bidirectional"))
    )
    (net (code "324") (name "unconnected-(U7B-PA8-PadCN12_23)") (class "Default")
      (node (ref "U7") (pin "CN12_23") (pinfunction "PA8_CN12_23") (pintype "bidirectional"))
    )
    (net (code "325") (name "unconnected-(U7B-PA9-PadCN12_21)") (class "Default")
      (node (ref "U7") (pin "CN12_21") (pinfunction "PA9_CN12_21") (pintype "bidirectional"))
    )
    (net (code "326") (name "unconnected-(U7B-PA10-PadCN12_33)") (class "Default")
      (node (ref "U7") (pin "CN12_33") (pinfunction "PA10_CN12_33") (pintype "bidirectional"))
    )
    (net (code "327") (name "unconnected-(U7B-PA11-PadCN12_14)") (class "Default")
      (node (ref "U7") (pin "CN12_14") (pinfunction "PA11_CN12_14") (pintype "bidirectional"))
    )
    (net (code "328") (name "unconnected-(U7B-PA12-PadCN12_12)") (class "Default")
      (node (ref "U7") (pin "CN12_12") (pinfunction "PA12_CN12_12") (pintype "bidirectional"))
    )
    (net (code "329") (name "unconnected-(U7B-PB1-PadCN12_24)") (class "Default")
      (node (ref "U7") (pin "CN12_24") (pinfunction "PB1_CN12_24") (pintype "bidirectional"))
    )
    (net (code "330") (name "unconnected-(U7B-PB2-PadCN12_22)") (class "Default")
      (node (ref "U7") (pin "CN12_22") (pinfunction "PB2_CN12_22") (pintype "bidirectional"))
    )
    (net (code "331") (name "unconnected-(U7B-PB3-PadCN12_31)") (class "Default")
      (node (ref "U7") (pin "CN12_31") (pinfunction "PB3_CN12_31") (pintype "bidirectional"))
    )
    (net (code "332") (name "unconnected-(U7B-PB4-PadCN12_27)") (class "Default")
      (node (ref "U7") (pin "CN12_27") (pinfunction "PB4_CN12_27") (pintype "bidirectional"))
    )
    (net (code "333") (name "unconnected-(U7B-PB5-PadCN12_29)") (class "Default")
      (node (ref "U7") (pin "CN12_29") (pinfunction "PB5_CN12_29") (pintype "bidirectional"))
    )
    (net (code "334") (name "unconnected-(U7B-PB6-PadCN12_17)") (class "Default")
      (node (ref "U7") (pin "CN12_17") (pinfunction "PB6_CN12_17") (pintype "bidirectional"))
    )
    (net (code "335") (name "unconnected-(U7B-PB8-PadCN12_3)") (class "Default")
      (node (ref "U7") (pin "CN12_3") (pinfunction "PB8_CN12_3") (pintype "bidirectional"))
    )
    (net (code "336") (name "unconnected-(U7B-PB9-PadCN12_5)") (class "Default")
      (node (ref "U7") (pin "CN12_5") (pinfunction "PB9_CN12_5") (pintype "bidirectional"))
    )
    (net (code "337") (name "unconnected-(U7B-PB10-PadCN12_25)") (class "Default")
      (node (ref "U7") (pin "CN12_25") (pinfunction "PB10_CN12_25") (pintype "bidirectional"))
    )
    (net (code "338") (name "unconnected-(U7B-PB11-PadCN12_18)") (class "Default")
      (node (ref "U7") (pin "CN12_18") (pinfunction "PB11_CN12_18") (pintype "bidirectional"))
    )
    (net (code "339") (name "unconnected-(U7B-PB12-PadCN12_16)") (class "Default")
      (node (ref "U7") (pin "CN12_16") (pinfunction "PB12_CN12_16") (pintype "bidirectional"))
    )
    (net (code "340") (name "unconnected-(U7B-PB13-PadCN12_30)") (class "Default")
      (node (ref "U7") (pin "CN12_30") (pinfunction "PB13_CN12_30") (pintype "bidirectional"))
    )
    (net (code "341") (name "unconnected-(U7B-PB14-PadCN12_28)") (class "Default")
      (node (ref "U7") (pin "CN12_28") (pinfunction "PB14_CN12_28") (pintype "bidirectional"))
    )
    (net (code "342") (name "unconnected-(U7B-PB15-PadCN12_26)") (class "Default")
      (node (ref "U7") (pin "CN12_26") (pinfunction "PB15_CN12_26") (pintype "bidirectional"))
    )
    (net (code "343") (name "unconnected-(U7B-PC4-PadCN12_34)") (class "Default")
      (node (ref "U7") (pin "CN12_34") (pinfunction "PC4_CN12_34") (pintype "bidirectional"))
    )
    (net (code "344") (name "unconnected-(U7B-PC5-PadCN12_6)") (class "Default")
      (node (ref "U7") (pin "CN12_6") (pinfunction "PC5_CN12_6") (pintype "bidirectional"))
    )
    (net (code "345") (name "unconnected-(U7B-PC6-PadCN12_4)") (class "Default")
      (node (ref "U7") (pin "CN12_4") (pinfunction "PC6_CN12_4") (pintype "bidirectional"))
    )
    (net (code "346") (name "unconnected-(U7B-PC7-PadCN12_19)") (class "Default")
      (node (ref "U7") (pin "CN12_19") (pinfunction "PC7_CN12_19") (pintype "bidirectional"))
    )
    (net (code "347") (name "unconnected-(U7B-PC8-PadCN12_2)") (class "Default")
      (node (ref "U7") (pin "CN12_2") (pinfunction "PC8_CN12_2") (pintype "bidirectional"))
    )
    (net (code "348") (name "unconnected-(U7B-PC9-PadCN12_1)") (class "Default")
      (node (ref "U7") (pin "CN12_1") (pinfunction "PC9_CN12_1") (pintype "bidirectional"))
    )
    (net (code "349") (name "unconnected-(U7B-PD8-PadCN12_10)") (class "Default")
      (node (ref "U7") (pin "CN12_10") (pinfunction "PD8_CN12_10") (pintype "bidirectional"))
    )
    (net (code "350") (name "unconnected-(U7B-PD10-PadCN12_65)") (class "Default")
      (node (ref "U7") (pin "CN12_65") (pinfunction "PD10_CN12_65") (pintype "bidirectional"))
    )
    (net (code "351") (name "unconnected-(U7B-PD11-PadCN12_45)") (class "Default")
      (node (ref "U7") (pin "CN12_45") (pinfunction "PD11_CN12_45") (pintype "bidirectional"))
    )
    (net (code "352") (name "unconnected-(U7B-PD12-PadCN12_43)") (class "Default")
      (node (ref "U7") (pin "CN12_43") (pinfunction "PD12_CN12_43") (pintype "bidirectional"))
    )
    (net (code "353") (name "unconnected-(U7B-PD13-PadCN12_41)") (class "Default")
      (node (ref "U7") (pin "CN12_41") (pinfunction "PD13_CN12_41") (pintype "bidirectional"))
    )
    (net (code "354") (name "unconnected-(U7B-PD14-PadCN12_46)") (class "Default")
      (node (ref "U7") (pin "CN12_46") (pinfunction "PD14_CN12_46") (pintype "bidirectional"))
    )
    (net (code "355") (name "unconnected-(U7B-PD15-PadCN12_48)") (class "Default")
      (node (ref "U7") (pin "CN12_48") (pinfunction "PD15_CN12_48") (pintype "bidirectional"))
    )
    (net (code "356") (name "unconnected-(U7B-PE0-PadCN12_64)") (class "Default")
      (node (ref "U7") (pin "CN12_64") (pinfunction "PE0_CN12_64") (pintype "bidirectional"))
    )
    (net (code "357") (name "unconnected-(U7B-PE7-PadCN12_44)") (class "Default")
      (node (ref "U7") (pin "CN12_44") (pinfunction "PE7_CN12_44") (pintype "bidirectional"))
    )
    (net (code "358") (name "unconnected-(U7B-PE8-PadCN12_40)") (class "Default")
      (node (ref "U7") (pin "CN12_40") (pinfunction "PE8_CN12_40") (pintype "bidirectional"))
    )
    (net (code "359") (name "unconnected-(U7B-PE9-PadCN12_52)") (class "Default")
      (node (ref "U7") (pin "CN12_52") (pinfunction "PE9_CN12_52") (pintype "bidirectional"))
    )
    (net (code "360") (name "unconnected-(U7B-PE10-PadCN12_47)") (class "Default")
      (node (ref "U7") (pin "CN12_47") (pinfunction "PE10_CN12_47") (pintype "bidirectional"))
    )
    (net (code "361") (name "unconnected-(U7B-PE11-PadCN12_56)") (class "Default")
      (node (ref "U7") (pin "CN12_56") (pinfunction "PE11_CN12_56") (pintype "bidirectional"))
    )
    (net (code "362") (name "unconnected-(U7B-PE12-PadCN12_49)") (class "Default")
      (node (ref "U7") (pin "CN12_49") (pinfunction "PE12_CN12_49") (pintype "bidirectional"))
    )
    (net (code "363") (name "unconnected-(U7B-PE13-PadCN12_55)") (class "Default")
      (node (ref "U7") (pin "CN12_55") (pinfunction "PE13_CN12_55") (pintype "bidirectional"))
    )
    (net (code "364") (name "unconnected-(U7B-PE14-PadCN12_51)") (class "Default")
      (node (ref "U7") (pin "CN12_51") (pinfunction "PE14_CN12_51") (pintype "bidirectional"))
    )
    (net (code "365") (name "unconnected-(U7B-PE15-PadCN12_53)") (class "Default")
      (node (ref "U7") (pin "CN12_53") (pinfunction "PE15_CN12_53") (pintype "bidirectional"))
    )
    (net (code "366") (name "unconnected-(U7B-PF3-PadCN12_58)") (class "Default")
      (node (ref "U7") (pin "CN12_58") (pinfunction "PF3_CN12_58") (pintype "bidirectional"))
    )
    (net (code "367") (name "unconnected-(U7B-PF4-PadCN12_38)") (class "Default")
      (node (ref "U7") (pin "CN12_38") (pinfunction "PF4_CN12_38") (pintype "bidirectional"))
    )
    (net (code "368") (name "unconnected-(U7B-PF5-PadCN12_36)") (class "Default")
      (node (ref "U7") (pin "CN12_36") (pinfunction "PF5_CN12_36") (pintype "bidirectional"))
    )
    (net (code "369") (name "unconnected-(U7B-PF10-PadCN12_42)") (class "Default")
      (node (ref "U7") (pin "CN12_42") (pinfunction "PF10_CN12_42") (pintype "bidirectional"))
    )
    (net (code "370") (name "unconnected-(U7B-PF11-PadCN12_62)") (class "Default")
      (node (ref "U7") (pin "CN12_62") (pinfunction "PF11_CN12_62") (pintype "bidirectional"))
    )
    (net (code "371") (name "unconnected-(U7B-PF12-PadCN12_59)") (class "Default")
      (node (ref "U7") (pin "CN12_59") (pinfunction "PF12_CN12_59") (pintype "bidirectional"))
    )
    (net (code "372") (name "unconnected-(U7B-PF13-PadCN12_57)") (class "Default")
      (node (ref "U7") (pin "CN12_57") (pinfunction "PF13_CN12_57") (pintype "bidirectional"))
    )
    (net (code "373") (name "unconnected-(U7B-PF14-PadCN12_50)") (class "Default")
      (node (ref "U7") (pin "CN12_50") (pinfunction "PF14_CN12_50") (pintype "bidirectional"))
    )
    (net (code "374") (name "unconnected-(U7B-PF15-PadCN12_60)") (class "Default")
      (node (ref "U7") (pin "CN12_60") (pinfunction "PF15_CN12_60") (pintype "bidirectional"))
    )
    (net (code "375") (name "unconnected-(U7B-PG4-PadCN12_69)") (class "Default")
      (node (ref "U7") (pin "CN12_69") (pinfunction "PG4_CN12_69") (pintype "bidirectional"))
    )
    (net (code "376") (name "unconnected-(U7B-PG5-PadCN12_68)") (class "Default")
      (node (ref "U7") (pin "CN12_68") (pinfunction "PG5_CN12_68") (pintype "bidirectional"))
    )
    (net (code "377") (name "unconnected-(U7B-PG6-PadCN12_70)") (class "Default")
      (node (ref "U7") (pin "CN12_70") (pinfunction "PG6_CN12_70") (pintype "bidirectional"))
    )
    (net (code "378") (name "unconnected-(U7B-PG7-PadCN12_67)") (class "Default")
      (node (ref "U7") (pin "CN12_67") (pinfunction "PG7_CN12_67") (pintype "bidirectional"))
    )
    (net (code "379") (name "unconnected-(U7B-PG8-PadCN12_66)") (class "Default")
      (node (ref "U7") (pin "CN12_66") (pinfunction "PG8_CN12_66") (pintype "bidirectional"))
    )
    (net (code "380") (name "unconnected-(U7B-PG14-PadCN12_61)") (class "Default")
      (node (ref "U7") (pin "CN12_61") (pinfunction "PG14_CN12_61") (pintype "bidirectional"))
    )
    (net (code "381") (name "unconnected-(U7B-U5V-PadCN12_8)") (class "Default")
      (node (ref "U7") (pin "CN12_8") (pinfunction "U5V_CN12_8") (pintype "power_in"))
    )
  )
)
